# SCH_Amplifier_2025-05-17.net
KiCad netlist of a schematic drawn in EasyEDA
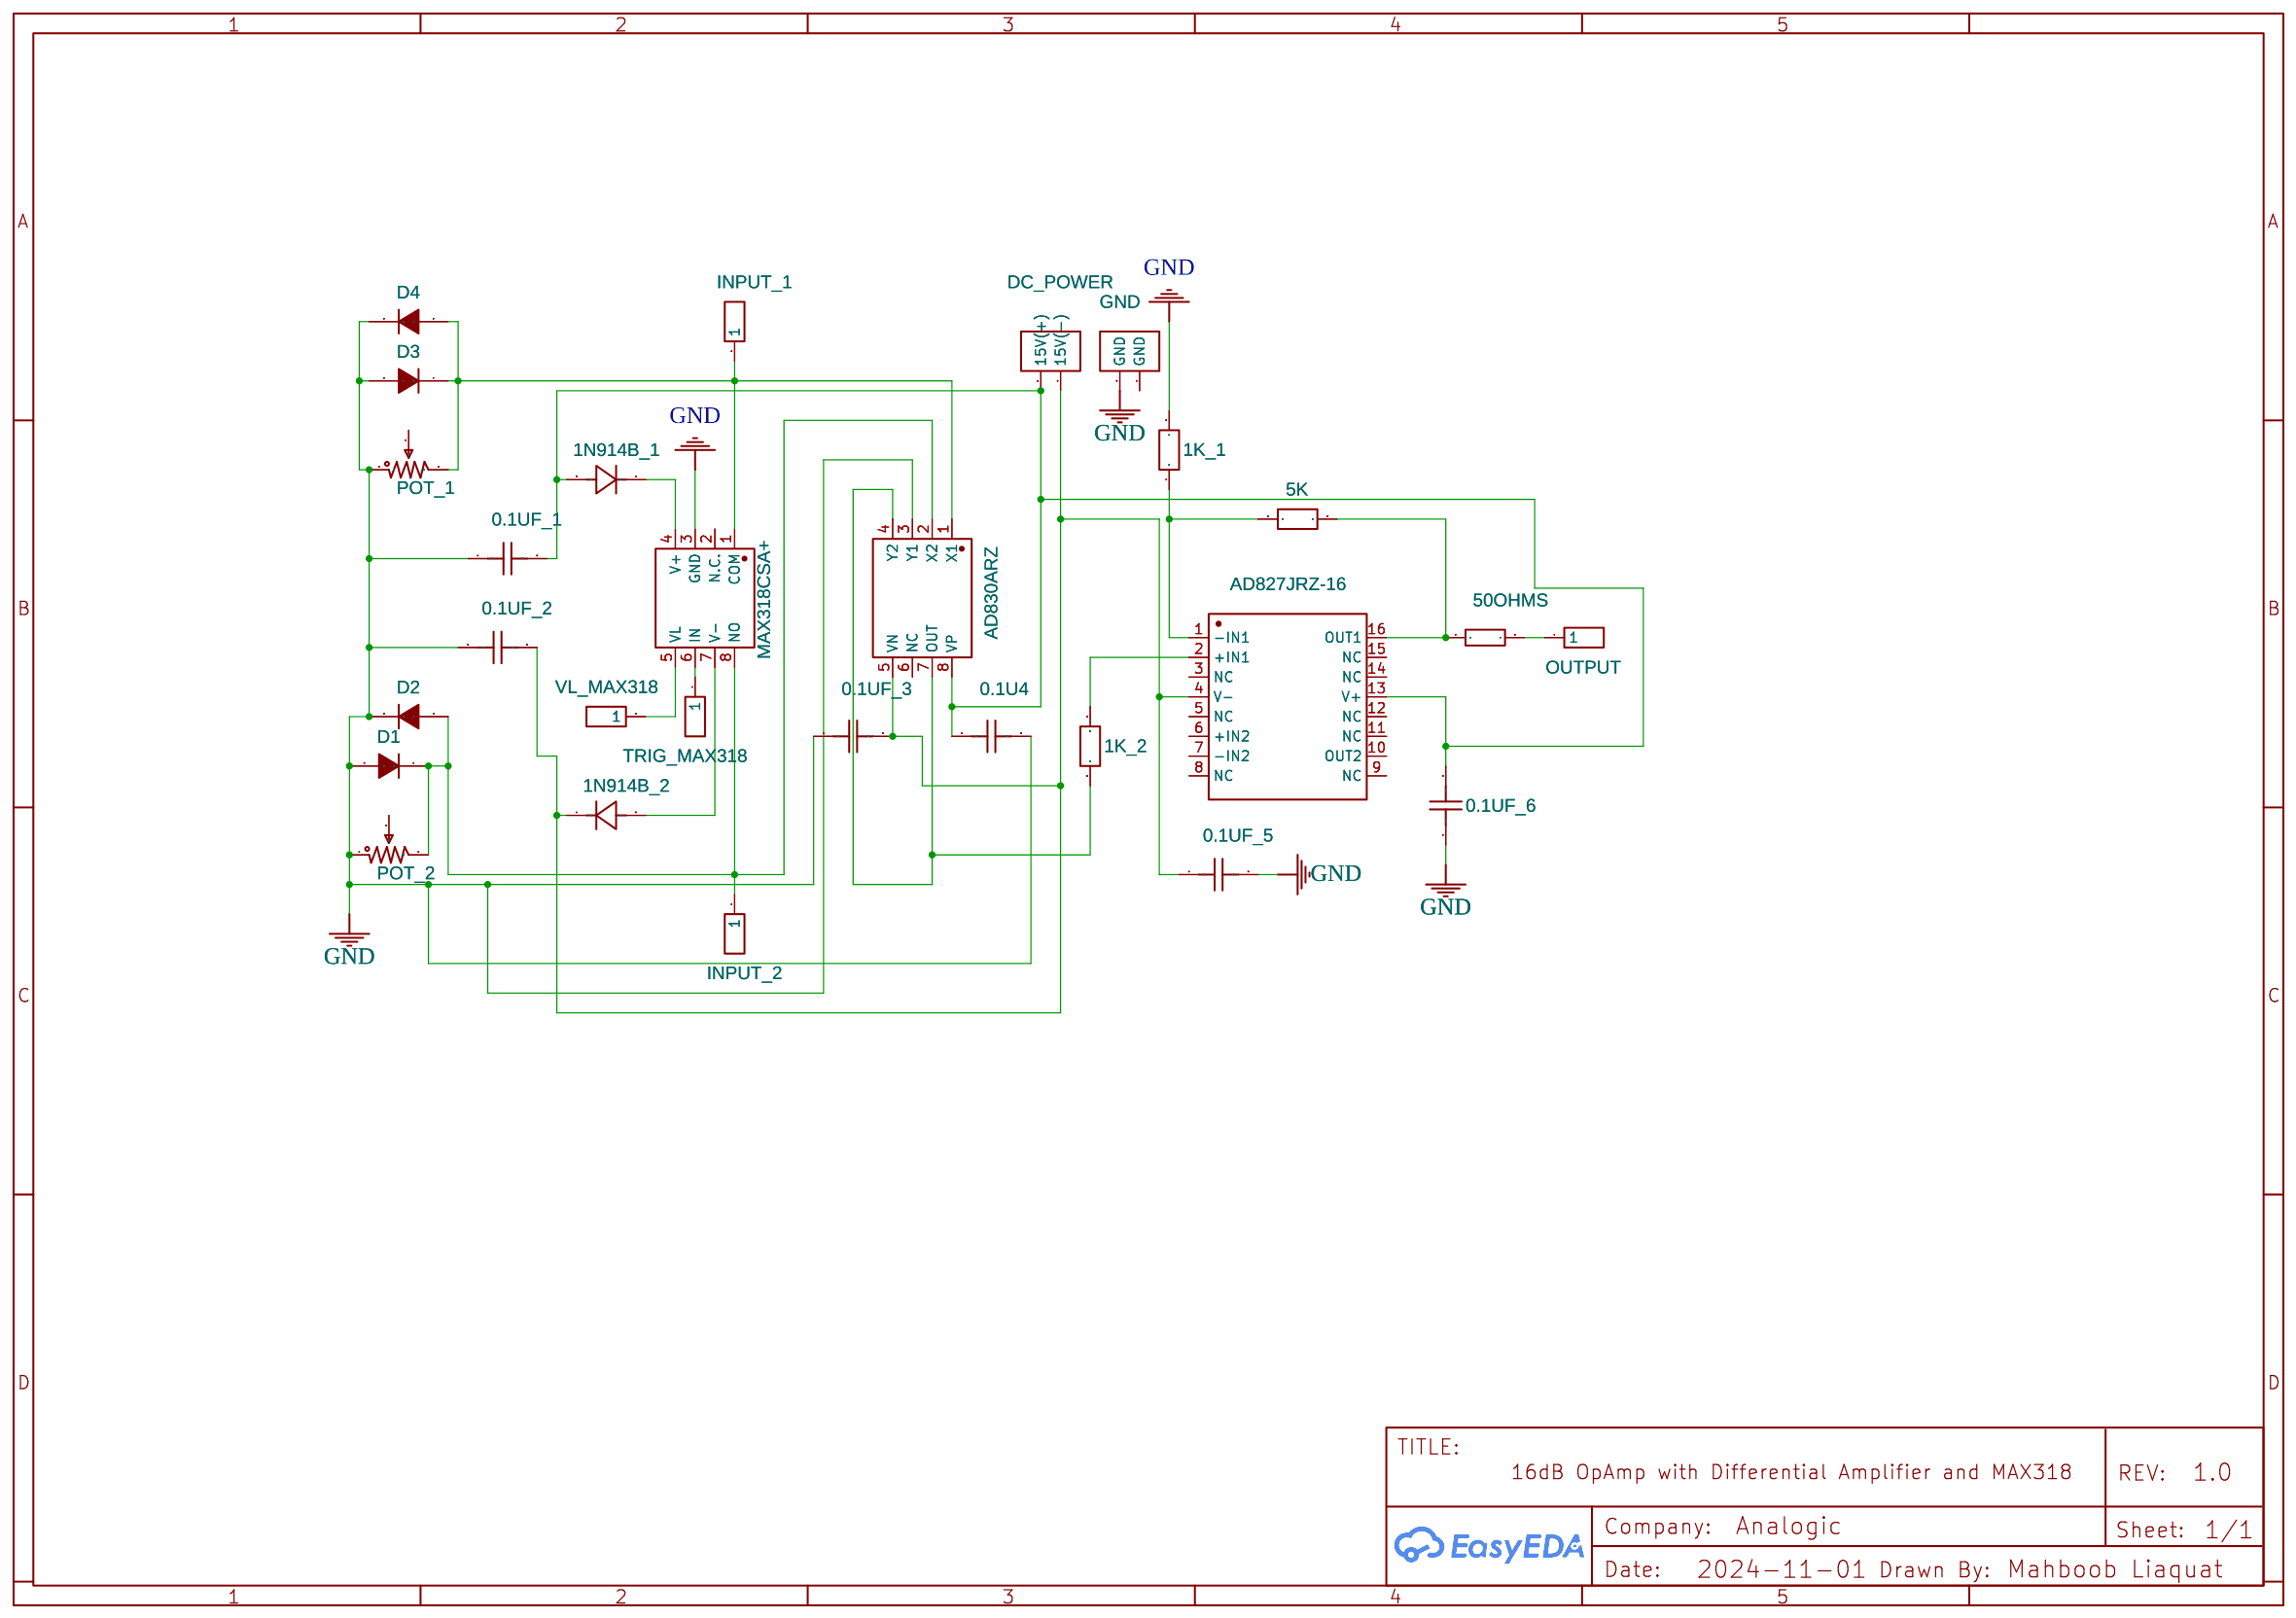
[diagram p0: schematic sheet]

(export (version "E")
  (design (tool "Eeschema 10.0.6"))
  (components
    (comp (ref "0.1U4")
      (value "100nF")
      (fields (field (name "Manufacturer Part") "C2012X7T2E104K125AE") (field (name "Manufacturer") "TDK"))
      (libsource (lib "") (part "C2012X7T2E104K125AE_2"))
    )
    (comp (ref "0.1UF_1")
      (value "100nF")
      (fields (field (name "Manufacturer Part") "C2012X7T2E104K125AE") (field (name "Manufacturer") "TDK"))
      (libsource (lib "") (part "C2012X7T2E104K125AE"))
    )
    (comp (ref "0.1UF_2")
      (value "100nF")
      (fields (field (name "Manufacturer Part") "C2012X7T2E104K125AE") (field (name "Manufacturer") "TDK"))
      (libsource (lib "") (part "C2012X7T2E104K125AE"))
    )
    (comp (ref "0.1UF_3")
      (value "100nF")
      (fields (field (name "Manufacturer Part") "C2012X7T2E104K125AE") (field (name "Manufacturer") "TDK"))
      (libsource (lib "") (part "C2012X7T2E104K125AE"))
    )
    (comp (ref "0.1UF_5")
      (value "100nF")
      (fields (field (name "Manufacturer Part") "C2012X7T2E104K125AE") (field (name "Manufacturer") "TDK"))
      (libsource (lib "") (part "C2012X7T2E104K125AE"))
    )
    (comp (ref "0.1UF_6")
      (value "100nF")
      (fields (field (name "Manufacturer Part") "C2012X7T2E104K125AE") (field (name "Manufacturer") "TDK"))
      (libsource (lib "") (part "C2012X7T2E104K125AE_1"))
    )
    (comp (ref "1K_1")
      (value "100mΩ")
      (fields
        (field (name "Manufacturer Part") "WSLP0603R1000DEA")
        (field (name "Manufacturer") "VISHAY(威世)")
      )
      (libsource (lib "") (part "WSLP0603R1000DEA"))
    )
    (comp (ref "1K_2")
      (value "100mΩ")
      (fields
        (field (name "Manufacturer Part") "WSLP0603R1000DEA")
        (field (name "Manufacturer") "VISHAY(威世)")
      )
      (libsource (lib "") (part "WSLP0603R1000DEA"))
    )
    (comp (ref "1N914B_1")
      (value "1N914B")
      (fields (field (name "Manufacturer") "onsemi(安森美)"))
      (libsource (lib "") (part "1N914B"))
    )
    (comp (ref "1N914B_2")
      (value "1N914B")
      (fields (field (name "Manufacturer") "onsemi(安森美)"))
      (libsource (lib "") (part "1N914B_1"))
    )
    (comp (ref "5K")
      (value "100mΩ")
      (fields
        (field (name "Manufacturer Part") "WSLP0603R1000DEA")
        (field (name "Manufacturer") "VISHAY(威世)")
      )
      (libsource (lib "") (part "WSLP0603R1000DEA_1"))
    )
    (comp (ref "50OHMS")
      (value "49.9Ω")
      (fields (field (name "Manufacturer Part") "RC1206FR-0749R9L") (field (name "Manufacturer") "YAGEO(国巨)"))
      (libsource (lib "") (part "RC1206FR-0749R9L"))
    )
    (comp (ref "AD827JRZ-16")
      (value "AD827JRZ-16")
      (fields (field (name "Manufacturer") "ADI(亚德诺)"))
      (libsource (lib "") (part "AD827JRZ-16"))
    )
    (comp (ref "AD830ARZ")
      (value "AD830ARZ")
      (fields (field (name "Manufacturer") "ADI(亚德诺)"))
      (libsource (lib "") (part "AD830ARZ"))
    )
    (comp (ref "D1")
      (value "1N4148TR")
      (fields (field (name "Manufacturer") "onsemi(安森美)"))
      (libsource (lib "") (part "1N4148TR_1"))
    )
    (comp (ref "D2")
      (value "1N4148TR")
      (fields (field (name "Manufacturer") "onsemi(安森美)"))
      (libsource (lib "") (part "1N4148TR"))
    )
    (comp (ref "D3")
      (value "1N4148TR")
      (fields (field (name "Manufacturer") "onsemi(安森美)"))
      (libsource (lib "") (part "1N4148TR_1"))
    )
    (comp (ref "D4")
      (value "1N4148TR")
      (fields (field (name "Manufacturer") "onsemi(安森美)"))
      (libsource (lib "") (part "1N4148TR"))
    )
    (comp (ref "DC_POWER")
      (value "282836-2")
      (fields (field (name "Manufacturer") "TE-Connectivity"))
      (libsource (lib "") (part "282836-2_1"))
    )
    (comp (ref "GND")
      (value "282836-2")
      (fields (field (name "Manufacturer") "TE-Connectivity"))
      (libsource (lib "") (part "282836-2"))
    )
    (comp (ref "INPUT_1") (value "HDR-M-2.54_1x1") (libsource (lib "") (part "HDR-M-2.54_1x1_3")))
    (comp (ref "INPUT_2") (value "HDR-M-2.54_1x1") (libsource (lib "") (part "HDR-M-2.54_1x1_2")))
    (comp (ref "MAX318CSA+")
      (value "MAX318CSA+")
      (fields (field (name "Manufacturer") "ADI(亚德诺)/MAXIM(美信)"))
      (libsource (lib "") (part "MAX318CSA+"))
    )
    (comp (ref "OUTPUT") (value "HDR-M-2.54_1x1") (libsource (lib "") (part "HDR-M-2.54_1x1_4")))
    (comp (ref "POT_1")
      (value "1MΩ")
      (fields (field (name "Manufacturer Part") "3361P-1-105") (field (name "Manufacturer") "BOCHEN(博晨)"))
      (libsource (lib "") (part "3361P-1-105"))
    )
    (comp (ref "POT_2")
      (value "1MΩ")
      (fields (field (name "Manufacturer Part") "3361P-1-105") (field (name "Manufacturer") "BOCHEN(博晨)"))
      (libsource (lib "") (part "3361P-1-105"))
    )
    (comp (ref "TRIG_MAX318") (value "HDR-M-2.54_1x1") (libsource (lib "") (part "HDR-M-2.54_1x1_1")))
    (comp (ref "VL_MAX318") (value "HDR-M-2.54_1x1") (libsource (lib "") (part "HDR-M-2.54_1x1")))
  )
  (nets
    (net (code "1") (name "GND") (class "Default")
      (node (ref "0.1U4") (pin "2") (pinfunction "2_2") (pintype "unspecified"))
      (node (ref "0.1UF_1") (pin "1") (pinfunction "1_1") (pintype "unspecified"))
      (node (ref "0.1UF_2") (pin "1") (pinfunction "1_1") (pintype "unspecified"))
      (node (ref "0.1UF_3") (pin "1") (pinfunction "1_1") (pintype "unspecified"))
      (node (ref "0.1UF_5") (pin "2") (pinfunction "2_2") (pintype "unspecified"))
      (node (ref "0.1UF_6") (pin "1") (pinfunction "1_1") (pintype "unspecified"))
      (node (ref "1K_1") (pin "2") (pinfunction "2_2") (pintype "unspecified"))
      (node (ref "AD830ARZ") (pin "3") (pinfunction "Y1_3") (pintype "unspecified"))
      (node (ref "D1") (pin "2") (pinfunction "A_2") (pintype "unspecified"))
      (node (ref "D2") (pin "1") (pinfunction "C_1") (pintype "unspecified"))
      (node (ref "D3") (pin "2") (pinfunction "A_2") (pintype "unspecified"))
      (node (ref "D4") (pin "1") (pinfunction "C_1") (pintype "unspecified"))
      (node (ref "GND") (pin "2") (pinfunction "GND_2") (pintype "unspecified"))
      (node (ref "MAX318CSA+") (pin "3") (pinfunction "GND_3") (pintype "unspecified"))
      (node (ref "POT_1") (pin "1") (pinfunction "1_1") (pintype "unspecified"))
      (node (ref "POT_2") (pin "1") (pinfunction "1_1") (pintype "unspecified"))
    )
    (net (code "2") (name "Net-(1N914B_1-A)") (class "Default")
      (node (ref "0.1U4") (pin "1") (pinfunction "1_1") (pintype "unspecified"))
      (node (ref "0.1UF_1") (pin "2") (pinfunction "2_2") (pintype "unspecified"))
      (node (ref "0.1UF_6") (pin "2") (pinfunction "2_2") (pintype "unspecified"))
      (node (ref "1N914B_1") (pin "2") (pinfunction "A_2") (pintype "unspecified"))
      (node (ref "AD827JRZ-16") (pin "13") (pinfunction "V+_13") (pintype "unspecified"))
      (node (ref "AD830ARZ") (pin "8") (pinfunction "VP_8") (pintype "unspecified"))
      (node (ref "DC_POWER") (pin "2") (pinfunction "15V(+)_2") (pintype "unspecified"))
    )
    (net (code "3") (name "Net-(1N914B_1-K)") (class "Default")
      (node (ref "1N914B_1") (pin "1") (pinfunction "K_1") (pintype "unspecified"))
      (node (ref "MAX318CSA+") (pin "4") (pinfunction "V+_4") (pintype "unspecified"))
    )
    (net (code "4") (name "Net-(1N914B_2-A)") (class "Default")
      (node (ref "1N914B_2") (pin "2") (pinfunction "A_2") (pintype "unspecified"))
      (node (ref "MAX318CSA+") (pin "7") (pinfunction "V-_7") (pintype "unspecified"))
    )
    (net (code "5") (name "Net-(1N914B_2-K)") (class "Default")
      (node (ref "0.1UF_2") (pin "2") (pinfunction "2_2") (pintype "unspecified"))
      (node (ref "0.1UF_3") (pin "2") (pinfunction "2_2") (pintype "unspecified"))
      (node (ref "0.1UF_5") (pin "1") (pinfunction "1_1") (pintype "unspecified"))
      (node (ref "1N914B_2") (pin "1") (pinfunction "K_1") (pintype "unspecified"))
      (node (ref "AD827JRZ-16") (pin "4") (pinfunction "V-_4") (pintype "unspecified"))
      (node (ref "AD830ARZ") (pin "5") (pinfunction "VN_5") (pintype "unspecified"))
      (node (ref "DC_POWER") (pin "1") (pinfunction "15V(-)_1") (pintype "unspecified"))
    )
    (net (code "6") (name "Net-(50OHMS-Pad2)") (class "Default")
      (node (ref "50OHMS") (pin "2") (pinfunction "2_2") (pintype "unspecified"))
      (node (ref "OUTPUT") (pin "1") (pinfunction "1_1") (pintype "input"))
    )
    (net (code "7") (name "Net-(AD827JRZ-16-+IN1)") (class "Default")
      (node (ref "1K_2") (pin "2") (pinfunction "2_2") (pintype "unspecified"))
      (node (ref "AD827JRZ-16") (pin "2") (pinfunction "+IN1_2") (pintype "unspecified"))
    )
    (net (code "8") (name "Net-(AD827JRZ-16--IN1)") (class "Default")
      (node (ref "1K_1") (pin "1") (pinfunction "1_1") (pintype "unspecified"))
      (node (ref "5K") (pin "1") (pinfunction "1_1") (pintype "unspecified"))
      (node (ref "AD827JRZ-16") (pin "1") (pinfunction "-IN1_1") (pintype "unspecified"))
    )
    (net (code "9") (name "Net-(AD827JRZ-16-OUT1)") (class "Default")
      (node (ref "50OHMS") (pin "1") (pinfunction "1_1") (pintype "unspecified"))
      (node (ref "5K") (pin "2") (pinfunction "2_2") (pintype "unspecified"))
      (node (ref "AD827JRZ-16") (pin "16") (pinfunction "OUT1_16") (pintype "unspecified"))
    )
    (net (code "10") (name "Net-(AD830ARZ-OUT)") (class "Default")
      (node (ref "1K_2") (pin "1") (pinfunction "1_1") (pintype "unspecified"))
      (node (ref "AD830ARZ") (pin "4") (pinfunction "Y2_4") (pintype "unspecified"))
      (node (ref "AD830ARZ") (pin "7") (pinfunction "OUT_7") (pintype "unspecified"))
    )
    (net (code "11") (name "Net-(AD830ARZ-X1)") (class "Default")
      (node (ref "AD830ARZ") (pin "1") (pinfunction "X1_1") (pintype "unspecified"))
      (node (ref "D3") (pin "1") (pinfunction "C_1") (pintype "unspecified"))
      (node (ref "D4") (pin "2") (pinfunction "A_2") (pintype "unspecified"))
      (node (ref "INPUT_1") (pin "1") (pinfunction "1_1") (pintype "input"))
      (node (ref "MAX318CSA+") (pin "1") (pinfunction "COM_1") (pintype "unspecified"))
      (node (ref "POT_1") (pin "3") (pinfunction "3_3") (pintype "unspecified"))
    )
    (net (code "12") (name "Net-(AD830ARZ-X2)") (class "Default")
      (node (ref "AD830ARZ") (pin "2") (pinfunction "X2_2") (pintype "unspecified"))
      (node (ref "D1") (pin "1") (pinfunction "C_1") (pintype "unspecified"))
      (node (ref "D2") (pin "2") (pinfunction "A_2") (pintype "unspecified"))
      (node (ref "INPUT_2") (pin "1") (pinfunction "1_1") (pintype "input"))
      (node (ref "MAX318CSA+") (pin "8") (pinfunction "NO_8") (pintype "unspecified"))
      (node (ref "POT_2") (pin "3") (pinfunction "3_3") (pintype "unspecified"))
    )
    (net (code "13") (name "Net-(MAX318CSA+-IN)") (class "Default")
      (node (ref "MAX318CSA+") (pin "6") (pinfunction "IN_6") (pintype "unspecified"))
      (node (ref "TRIG_MAX318") (pin "1") (pinfunction "1_1") (pintype "input"))
    )
    (net (code "14") (name "Net-(MAX318CSA+-VL)") (class "Default")
      (node (ref "MAX318CSA+") (pin "5") (pinfunction "VL_5") (pintype "unspecified"))
      (node (ref "VL_MAX318") (pin "1") (pinfunction "1_1") (pintype "input"))
    )
    (net (code "15") (name "unconnected-(AD827JRZ-16-+IN2-Pad6)") (class "Default")
      (node (ref "AD827JRZ-16") (pin "6") (pinfunction "+IN2_6") (pintype "unspecified"))
    )
    (net (code "16") (name "unconnected-(AD827JRZ-16--IN2-Pad7)") (class "Default")
      (node (ref "AD827JRZ-16") (pin "7") (pinfunction "-IN2_7") (pintype "unspecified"))
    )
    (net (code "17") (name "unconnected-(AD827JRZ-16-NC-Pad3)") (class "Default")
      (node (ref "AD827JRZ-16") (pin "3") (pinfunction "NC_3") (pintype "unspecified"))
    )
    (net (code "18") (name "unconnected-(AD827JRZ-16-NC-Pad5)") (class "Default")
      (node (ref "AD827JRZ-16") (pin "5") (pinfunction "NC_5") (pintype "unspecified"))
    )
    (net (code "19") (name "unconnected-(AD827JRZ-16-NC-Pad8)") (class "Default")
      (node (ref "AD827JRZ-16") (pin "8") (pinfunction "NC_8") (pintype "unspecified"))
    )
    (net (code "20") (name "unconnected-(AD827JRZ-16-NC-Pad9)") (class "Default")
      (node (ref "AD827JRZ-16") (pin "9") (pinfunction "NC_9") (pintype "unspecified"))
    )
    (net (code "21") (name "unconnected-(AD827JRZ-16-NC-Pad11)") (class "Default")
      (node (ref "AD827JRZ-16") (pin "11") (pinfunction "NC_11") (pintype "unspecified"))
    )
    (net (code "22") (name "unconnected-(AD827JRZ-16-NC-Pad12)") (class "Default")
      (node (ref "AD827JRZ-16") (pin "12") (pinfunction "NC_12") (pintype "unspecified"))
    )
    (net (code "23") (name "unconnected-(AD827JRZ-16-NC-Pad14)") (class "Default")
      (node (ref "AD827JRZ-16") (pin "14") (pinfunction "NC_14") (pintype "unspecified"))
    )
    (net (code "24") (name "unconnected-(AD827JRZ-16-NC-Pad15)") (class "Default")
      (node (ref "AD827JRZ-16") (pin "15") (pinfunction "NC_15") (pintype "unspecified"))
    )
    (net (code "25") (name "unconnected-(AD827JRZ-16-OUT2-Pad10)") (class "Default")
      (node (ref "AD827JRZ-16") (pin "10") (pinfunction "OUT2_10") (pintype "unspecified"))
    )
    (net (code "26") (name "unconnected-(AD830ARZ-NC-Pad6)") (class "Default")
      (node (ref "AD830ARZ") (pin "6") (pinfunction "NC_6") (pintype "unspecified"))
    )
    (net (code "27") (name "unconnected-(GND-GND-Pad1)") (class "Default")
      (node (ref "GND") (pin "1") (pinfunction "GND_1") (pintype "unspecified"))
    )
    (net (code "28") (name "unconnected-(MAX318CSA+-N.C.-Pad2)") (class "Default")
      (node (ref "MAX318CSA+") (pin "2") (pinfunction "N.C._2") (pintype "unspecified"))
    )
    (net (code "29") (name "unconnected-(POT_1-Pad2)") (class "Default")
      (node (ref "POT_1") (pin "2") (pinfunction "2_2") (pintype "unspecified"))
    )
    (net (code "30") (name "unconnected-(POT_2-Pad2)") (class "Default")
      (node (ref "POT_2") (pin "2") (pinfunction "2_2") (pintype "unspecified"))
    )
  )
)
